# Power_Managment.net
KiCad netlist of a schematic drawn in Altium Designer
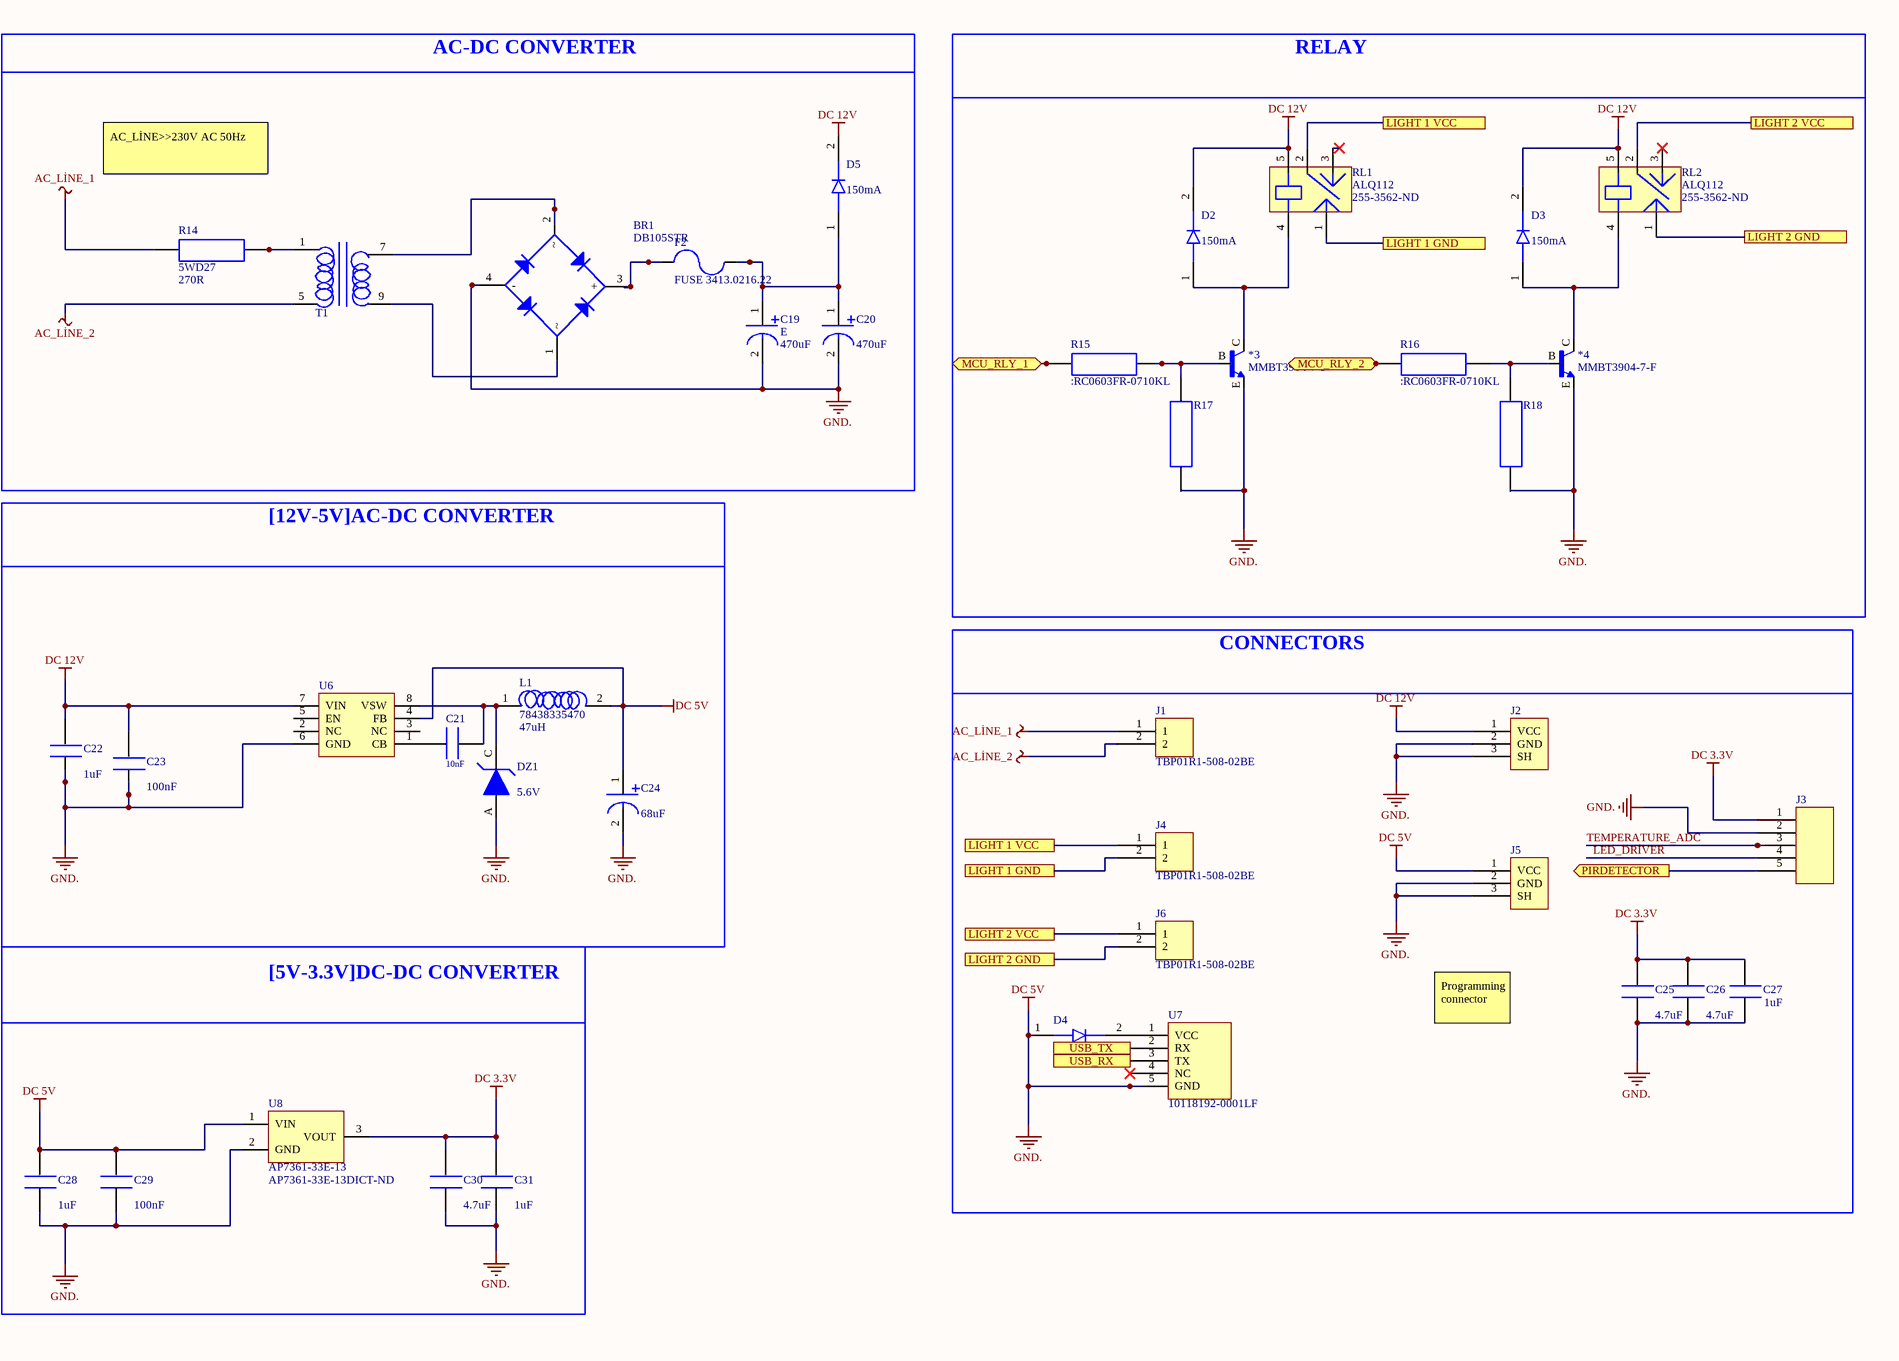
[diagram p0: Power Managment+.SchDoc, right]

(export (version "E")
  (design (tool "Eeschema 10.0.6"))
  (components
    (comp (ref "*3")
      (value "MMBT3904-7-F")
      (footprint "SOT23_F")
      (description "Transistor General Purpose BJT NPN 40 Volt 0.2A Automotive 3-Pin SOT-23")
      (fields (field (name "MANUFACTURER") "Diodes Zetex"))
      (libsource (lib "ALTİUM_PROJE.Integrated_Library1") (part "TRANS NPN 40V 0.2A SMD SOT23-3"))
    )
    (comp (ref "*4")
      (value "MMBT3904-7-F")
      (footprint "SOT23_F")
      (description "Transistor General Purpose BJT NPN 40 Volt 0.2A Automotive 3-Pin SOT-23")
      (fields (field (name "MANUFACTURER") "Diodes Zetex"))
      (libsource (lib "ALTİUM_PROJE.Integrated_Library1") (part "TRANS NPN 40V 0.2A SMD SOT23-3"))
    )
    (comp (ref "BR1")
      (value "DB105STR")
      (footprint "DB105STR")
      (description "Bridge Rect 1PHASE 600V 1A Db-s")
      (fields (field (name "MANUFACTURER") "Sangdest Microelectronics"))
      (libsource (lib "ALTİUM_PROJE.Integrated_Library1") (part "DB105STR"))
    )
    (comp (ref "C19")
      (value "E")
      (footprint "CAP_RADİAL_D10_P5")
      (description "Cap, 470UF, 50V, Alu Elec, Radial")
      (fields
        (field (name "MANUFACTURER") "KEMET")
        (field (name "MANUFACTURER PART NUMBER") "ESH477M050AH4AA")
        (field (name "CAPACITANCE") "470uF")
      )
      (libsource (lib "ALTİUM_PROJE.Integrated_Library1") (part "Cap, 470UF, 50V,"))
    )
    (comp (ref "C20")
      (value "ESH477M050AH4AA")
      (footprint "CAP_RADİAL_D10_P5")
      (description "Cap, 470UF, 50V, Alu Elec, Radial")
      (fields
        (field (name "MANUFACTURER") "KEMET")
        (field (name "TOLERANCE") "20%")
        (field (name "CAPACITANCE") "470uF")
      )
      (libsource (lib "ALTİUM_PROJE.Integrated_Library1") (part "Cap, 470UF, 50V,"))
    )
    (comp (ref "C21")
      (value "0603B103K160CT")
      (footprint "CAP_0603")
      (description "CAP CER 0603 0.01 F, 10%,")
      (fields
        (field (name "MANUFACTURER") "Walsin Technologies")
        (field (name "TOLERANCE") "10%")
        (field (name "CAPACITANCE") "10nF")
      )
      (libsource (lib "ALTİUM_PROJE.Integrated_Library1") (part "CAP CER 10nF"))
    )
    (comp (ref "C22")
      (value "CL21B105KBFNNNE")
      (footprint "CAP 0805")
      (description "Ceramic capacitor SMD-0805      %10 1UF")
      (fields
        (field (name "MANUFACTURER") "Samsung")
        (field (name "TOLERANCE") "10%")
        (field (name "CAPACITANCE") "1uF")
      )
      (libsource (lib "ALTİUM_PROJE.Integrated_Library1") (part "CAP CER 1UF"))
    )
    (comp (ref "C23")
      (value "C0603C104K5RACTU")
      (footprint "CAP_0603")
      (description "CAP CEP 100nF %10 0603 SMD")
      (fields
        (field (name "MANUFACTURER") "KEMET")
        (field (name "TOLERANCE") "10%")
        (field (name "CAPACITANCE") "100nF")
      )
      (libsource (lib "ALTİUM_PROJE.Integrated_Library1") (part "CAP CEP 100nF 0603"))
    )
    (comp (ref "C24")
      (value "EEV686M035A9HAA")
      (footprint "CAP_EEV")
      (description "Cap Aluminum Lytic 68uF 35V 20% (6.3 X 7.7mm) SMD 280mA 2000h 105C T/R")
      (fields
        (field (name "MANUFACTURER") "KEMET")
        (field (name "TOLERANCE") "20%")
        (field (name "CAPACITANCE") "68uF")
      )
      (libsource (lib "ALTİUM_PROJE.Integrated_Library1") (part "CAP ALUM 68UF 20% 35V SMD"))
    )
    (comp (ref "C25")
      (value "CL21A475KAQNNNE")
      (footprint "CAP 0805")
      (description "Cap Cer 4.7uF %10 0805")
      (fields
        (field (name "MANUFACTURER") "Samsung")
        (field (name "TOLERANCE") "10%")
        (field (name "CAPACITANCE") "4.7uF")
      )
      (libsource (lib "ALTİUM_PROJE.Integrated_Library1") (part "CAP CER_0805"))
    )
    (comp (ref "C26")
      (value "CL21A475KAQNNNE")
      (footprint "CAP 0805")
      (description "Cap Cer 4.7uF %10 0805")
      (fields
        (field (name "MANUFACTURER") "Samsung")
        (field (name "TOLERANCE") "10%")
        (field (name "CAPACITANCE") "4.7uF")
      )
      (libsource (lib "ALTİUM_PROJE.Integrated_Library1") (part "CAP CER_0805"))
    )
    (comp (ref "C27")
      (value "CL21B105KBFNNNE")
      (footprint "CAP 0805")
      (description "Ceramic capacitor SMD-0805      %10 1UF")
      (fields
        (field (name "MANUFACTURER") "Samsung")
        (field (name "TOLERANCE") "10%")
        (field (name "CAPACITANCE") "1uF")
      )
      (libsource (lib "ALTİUM_PROJE.Integrated_Library1") (part "CAP CER 1UF"))
    )
    (comp (ref "C28")
      (value "CL21B105KBFNNNE")
      (footprint "CAP 0805")
      (description "Ceramic capacitor SMD-0805      %10 1UF")
      (fields
        (field (name "MANUFACTURER") "Samsung")
        (field (name "TOLERANCE") "10%")
        (field (name "CAPACITANCE") "1uF")
      )
      (libsource (lib "ALTİUM_PROJE.Integrated_Library1") (part "CAP CER 1UF"))
    )
    (comp (ref "C29")
      (value "C0603C104K5RACTU")
      (footprint "CAP_0603")
      (description "CAP CEP 100nF %10 0603 SMD")
      (fields
        (field (name "MANUFACTURER") "KEMET")
        (field (name "TOLERANCE") "10%")
        (field (name "CAPACITANCE") "100nF")
      )
      (libsource (lib "ALTİUM_PROJE.Integrated_Library1") (part "CAP CEP 100nF 0603"))
    )
    (comp (ref "C30")
      (value "CL21A475KAQNNNE")
      (footprint "CAP 0805")
      (description "Cap Cer 4.7uF %10 0805")
      (fields
        (field (name "MANUFACTURER") "Samsung")
        (field (name "TOLERANCE") "10%")
        (field (name "CAPACITANCE") "4.7uF")
      )
      (libsource (lib "ALTİUM_PROJE.Integrated_Library1") (part "CAP CER_0805"))
    )
    (comp (ref "C31")
      (value "CL21B105KBFNNNE")
      (footprint "CAP 0805")
      (description "Ceramic capacitor SMD-0805      %10 1UF")
      (fields
        (field (name "MANUFACTURER") "Samsung")
        (field (name "TOLERANCE") "10%")
        (field (name "CAPACITANCE") "1uF")
      )
      (libsource (lib "ALTİUM_PROJE.Integrated_Library1") (part "CAP CER 1UF"))
    )
    (comp (ref "D2")
      (value "1N4148WS")
      (footprint "DİODE GEN")
      (description "Diode Small Signal Switching 100V 0.15A Automotive 2-Pin SOD-323F T/R")
      (fields
        (field (name "MANUFACTURER") "ON Semiconductor / Fairchild")
        (field (name "AVERAGE RECTIFIED CURRENT") "150mA")
      )
      (libsource (lib "ALTİUM_PROJE.Integrated_Library1") (part "DIODE GEN PURP 75V 150MA SOD323F"))
    )
    (comp (ref "D3")
      (value "1N4148WS")
      (footprint "DİODE GEN")
      (description "Diode Small Signal Switching 100V 0.15A Automotive 2-Pin SOD-323F T/R")
      (fields
        (field (name "MANUFACTURER") "ON Semiconductor / Fairchild")
        (field (name "AVERAGE RECTIFIED CURRENT") "150mA")
      )
      (libsource (lib "ALTİUM_PROJE.Integrated_Library1") (part "DIODE GEN PURP 75V 150MA SOD323F"))
    )
    (comp (ref "D4")
      (value "1N4148WS")
      (footprint "DİODE GEN")
      (description "Diode Small Signal Switching 100V 0.15A Automotive 2-Pin SOD-323F T/R")
      (fields (field (name "MANUFACTURER") "ON Semiconductor / Fairchild"))
      (libsource (lib "ALTİUM_PROJE.Integrated_Library1") (part "DIODE GEN PURP 75V 150MA SOD323F"))
    )
    (comp (ref "D5")
      (value "1N4148WS")
      (footprint "DİODE GEN")
      (description "Diode Small Signal Switching 100V 0.15A Automotive 2-Pin SOD-323F T/R")
      (fields
        (field (name "MANUFACTURER") "ON Semiconductor / Fairchild")
        (field (name "AVERAGE RECTIFIED CURRENT") "150mA")
      )
      (libsource (lib "ALTİUM_PROJE.Integrated_Library1") (part "DIODE GEN PURP 75V 150MA SOD323F"))
    )
    (comp (ref "DZ1")
      (value "Zener Diode 5.6V SMB")
      (footprint "ZEN DİOED SMD")
      (description "Diode, Zener, Vr 5.6V, If 200mA, Pkg SMB, Vf 1.5V, Tj +150degc, Pd 3W, Ir 66.9mA")
      (fields
        (field (name "MANUFACTURER") "ON Semiconductor")
        (field (name "MANUFACTURER PART NUMBER") "1SMB5919BT3G")
        (field (name "ZENER VOLTAGE") "5.6V")
      )
      (libsource (lib "ALTİUM_PROJE.Integrated_Library1") (part "Zener Diode 5.6V SMB"))
    )
    (comp (ref "F1")
      (value "FUSE 3413.0216.22")
      (footprint "FUSE 3413.0216.22")
      (description "Fuse Chip Fast Acting 1A 32V SMD Solder Pad 1206 Glass T/R VDE/cULus")
      (fields
        (field (name "MANUFACTURER") "Schurter")
        (field (name "MANUFACTURER PART NUMBER") "3413.0216.22")
      )
      (libsource (lib "ALTİUM_PROJE.Integrated_Library1") (part "FUSE 3413.0216.22"))
    )
    (comp (ref "F2")
      (value "FUSE 3413.0216.22")
      (footprint "FUSE 3413.0216.22")
      (description "Fuse Chip Fast Acting 1A 32V SMD Solder Pad 1206 Glass T/R VDE/cULus")
      (fields
        (field (name "MANUFACTURER") "Schurter")
        (field (name "MANUFACTURER PART NUMBER") "3413.0216.22")
      )
      (libsource (lib "ALTİUM_PROJE.Integrated_Library1") (part "FUSE 3413.0216.22"))
    )
    (comp (ref "J1")
      (value "TBP01R1-508-02BE")
      (footprint "TERMINAL BLOCK")
      (description "2~24 Poles, Pluggable, Receptacle, Horizontal, 5.08 Pitch, Terminal Block Connector")
      (fields (field (name "MANUFACTURER") "CUI Devices"))
      (libsource (lib "ALTİUM_PROJE.Integrated_Library1") (part "TERMINAL BLOCK"))
    )
    (comp (ref "J2")
      (value "PJ-037AH-SMT-TR")
      (footprint "jack")
      (description "2.0 x 6.3 mm, 5.0 A, Horizontal, Surface Mount (SMT), Dc Power Jack Connector")
      (fields (field (name "MANUFACTURER") "CUI"))
      (libsource (lib "ALTİUM_PROJE.Integrated_Library1") (part "PJ-037AH-SMT-TR"))
    )
    (comp (ref "J3")
      (value "SMH-105-02-L-S")
      (footprint "SMH-105")
      (description ".100 C.L. HORIZONTAL SMT SOCKET")
      (fields (field (name "MANUFACTURER") "Samtec"))
      (libsource (lib "ALTİUM_PROJE.Integrated_Library1") (part "PRO CONNECTER"))
    )
    (comp (ref "J4")
      (value "TBP01R1-508-02BE")
      (footprint "TERMINAL BLOCK")
      (description "2~24 Poles, Pluggable, Receptacle, Horizontal, 5.08 Pitch, Terminal Block Connector")
      (fields (field (name "MANUFACTURER") "CUI Devices"))
      (libsource (lib "ALTİUM_PROJE.Integrated_Library1") (part "TERMINAL BLOCK"))
    )
    (comp (ref "J5")
      (value "PJ-037AH-SMT-TR")
      (footprint "jack")
      (description "2.0 x 6.3 mm, 5.0 A, Horizontal, Surface Mount (SMT), Dc Power Jack Connector")
      (fields (field (name "MANUFACTURER") "CUI"))
      (libsource (lib "ALTİUM_PROJE.Integrated_Library1") (part "PJ-037AH-SMT-TR"))
    )
    (comp (ref "J6")
      (value "TBP01R1-508-02BE")
      (footprint "TERMINAL BLOCK")
      (description "2~24 Poles, Pluggable, Receptacle, Horizontal, 5.08 Pitch, Terminal Block Connector")
      (fields (field (name "MANUFACTURER") "CUI Devices"))
      (libsource (lib "ALTİUM_PROJE.Integrated_Library1") (part "TERMINAL BLOCK"))
    )
    (comp (ref "L1")
      (value "78438335470")
      (footprint "78438335470")
      (description "Fixed Ind 47UH 390MA 2.3 Ohm SMD")
      (fields
        (field (name "MANUFACTURER") "Wurth Electronics")
        (field (name "TOLERANCE") "30%")
        (field (name "INDUCTANCE") "47uH")
      )
      (libsource (lib "ALTİUM_PROJE.Integrated_Library1") (part "IND 47uH"))
    )
    (comp (ref "R14")
      (value "5WD27")
      (footprint "5WD27")
      (description "Resistor 5 Watt Cermet Wirewound Flameproof .27 Ohm 5% Axial Lead")
      (fields
        (field (name "MANUFACTURER") "NTE Electronics")
        (field (name "TOLERANCE") "5%")
        (field (name "RESISTANCE") "270R")
      )
      (libsource (lib "ALTİUM_PROJE.Integrated_Library1") (part "RES 0.27 OHM 5% 5W AXIAL"))
    )
    (comp (ref "R15")
      (value ":RC0603FR-0710KL")
      (footprint "RES_0603")
      (description "RES 10K %1 OHM 0603 SMD")
      (fields
        (field (name "MANUFACTURER") "Yageo")
        (field (name "MANUFACTURER PART NUMBER") "RC0603FR-0710KL")
      )
      (libsource (lib "") (part "RES 10K OHM 0603_1"))
    )
    (comp (ref "R16")
      (value ":RC0603FR-0710KL")
      (footprint "RES_0603")
      (description "RES 10K %1 OHM 0603 SMD")
      (fields
        (field (name "MANUFACTURER") "Yageo")
        (field (name "MANUFACTURER PART NUMBER") "RC0603FR-0710KL")
      )
      (libsource (lib "") (part "RES 10K OHM 0603_1"))
    )
    (comp (ref "R17")
      (value ":RC0603FR-0710KL")
      (footprint "RES_0603")
      (description "RES 10K %1 OHM 0603 SMD")
      (fields
        (field (name "MANUFACTURER") "Yageo")
        (field (name "MANUFACTURER PART NUMBER") "RC0603FR-0710KL")
      )
      (libsource (lib "ALTİUM_PROJE.Integrated_Library1") (part "RES 10K OHM 0603"))
    )
    (comp (ref "R18")
      (value ":RC0603FR-0710KL")
      (footprint "RES_0603")
      (description "RES 10K %1 OHM 0603 SMD")
      (fields
        (field (name "MANUFACTURER") "Yageo")
        (field (name "MANUFACTURER PART NUMBER") "RC0603FR-0710KL")
      )
      (libsource (lib "ALTİUM_PROJE.Integrated_Library1") (part "RES 10K OHM 0603"))
    )
    (comp (ref "RL1")
      (value "ALQ112")
      (footprint "ALQ112")
      (description "PANASONIC - ALQ112 - POWER RELAY, SPDT, 12VDC, 10A, THD")
      (fields (field (name "MANUFACTURER") "Panasonic") (field (name "SUPPLIER PART NUMBER 1") "255-3562-ND"))
      (libsource (lib "ALTİUM_PROJE.Integrated_Library1") (part "ALQ112"))
    )
    (comp (ref "RL2")
      (value "ALQ112")
      (footprint "ALQ112")
      (description "PANASONIC - ALQ112 - POWER RELAY, SPDT, 12VDC, 10A, THD")
      (fields (field (name "MANUFACTURER") "Panasonic") (field (name "SUPPLIER PART NUMBER 1") "255-3562-ND"))
      (libsource (lib "ALTİUM_PROJE.Integrated_Library1") (part "ALQ112"))
    )
    (comp (ref "T1")
      (value "BV302S12010-ZU")
      (footprint "BV302S12010-ZU")
      (description "Pwr Xfmr Laminated 1VA Th")
      (fields (field (name "MANUFACTURER") "Zettler Magnetics"))
      (libsource (lib "ALTİUM_PROJE.Integrated_Library1") (part "BV302S12010-ZU"))
    )
    (comp (ref "U6")
      (value "LM2675MX-12/NOPB")
      (footprint "SOIC8")
      (description "SIMPLE SWITCHER® 6.5V to 40V, 1A Low Component Count Step-Down Regulator 8-SOIC -40 to 125")
      (fields (field (name "MANUFACTURER") "TI National Semiconductor"))
      (libsource (lib "ALTİUM_PROJE.Integrated_Library1") (part "LM2675MX-12/NOPB"))
    )
    (comp (ref "U7")
      (value "10118192-0001LF")
      (footprint "MICRO USB")
      (description "FCI Right Angle Surface  USB 100 V ac; 1.8A")
      (fields (field (name "MANUFACTURER") "Amphenol ICC / FCI"))
      (libsource (lib "ALTİUM_PROJE.Integrated_Library1") (part "Micro USB"))
    )
    (comp (ref "U8")
      (value "AP7361-33E-13")
      (footprint "AP7361-33E-13")
      (description "AP7361 Series 3.3 V 1 A Low SMT Dropout Fixed-Mode Regulator - SOT-223")
      (fields
        (field (name "MANUFACTURER") "Diodes")
        (field (name "SUPPLIER PART NUMBER 1") "AP7361-33E-13DICT-ND")
      )
      (libsource (lib "ALTİUM_PROJE.Integrated_Library1") (part "AP7361-33E-13"))
    )
  )
  (nets
    (net (code "1") (name "/LED_DRİVER") (class "Default")
      (node (ref "J3") (pin "4") (pinfunction "4_4") (pintype "passive"))
    )
    (net (code "2") (name "/LIGHT 1 GND") (class "Default")
      (node (ref "J4") (pin "2") (pinfunction "2_2") (pintype "passive"))
      (node (ref "RL1") (pin "1") (pintype "passive"))
    )
    (net (code "3") (name "/LIGHT 1 VCC") (class "Default")
      (node (ref "J4") (pin "1") (pinfunction "1_1") (pintype "passive"))
      (node (ref "RL1") (pin "2") (pintype "passive"))
    )
    (net (code "4") (name "/LIGHT 2 GND") (class "Default")
      (node (ref "J6") (pin "2") (pinfunction "2_2") (pintype "passive"))
      (node (ref "RL2") (pin "1") (pintype "passive"))
    )
    (net (code "5") (name "/LIGHT 2 VCC") (class "Default")
      (node (ref "J6") (pin "1") (pinfunction "1_1") (pintype "passive"))
      (node (ref "RL2") (pin "2") (pintype "passive"))
    )
    (net (code "6") (name "/MCU_RLY_1") (class "Default")
      (node (ref "R15") (pin "1") (pinfunction "24_1") (pintype "passive"))
    )
    (net (code "8") (name "/PIRDETECTOR") (class "Default")
      (node (ref "J3") (pin "5") (pinfunction "5_5") (pintype "passive"))
    )
    (net (code "9") (name "/TEMPERATURE_ADC") (class "Default")
      (node (ref "J3") (pin "3") (pinfunction "3_3") (pintype "passive"))
    )
    (net (code "10") (name "/USB_RX") (class "Default")
      (node (ref "U7") (pin "3") (pinfunction "TX_3") (pintype "passive"))
    )
    (net (code "11") (name "/USB_TX") (class "Default")
      (node (ref "U7") (pin "2") (pinfunction "RX_2") (pintype "passive"))
    )
    (net (code "12") (name "AC_LİNE_1") (class "Default")
      (node (ref "J1") (pin "1") (pinfunction "1_1") (pintype "passive"))
      (node (ref "R14") (pin "1") (pinfunction "24_1") (pintype "passive"))
    )
    (net (code "13") (name "AC_LİNE_2") (class "Default")
      (node (ref "J1") (pin "2") (pinfunction "2_2") (pintype "passive"))
      (node (ref "T1") (pin "5") (pintype "passive"))
    )
    (net (code "14") (name "DC 3.3V") (class "Default")
      (node (ref "C25") (pin "2") (pinfunction "29_2") (pintype "passive"))
      (node (ref "C26") (pin "2") (pinfunction "29_2") (pintype "passive"))
      (node (ref "C27") (pin "2") (pinfunction "29_2") (pintype "passive"))
      (node (ref "C30") (pin "2") (pinfunction "29_2") (pintype "passive"))
      (node (ref "C31") (pin "2") (pinfunction "29_2") (pintype "passive"))
      (node (ref "J3") (pin "1") (pinfunction "1_1") (pintype "passive"))
      (node (ref "U8") (pin "3") (pinfunction "VOUT_3") (pintype "passive"))
    )
    (net (code "15") (name "DC 5V") (class "Default")
      (node (ref "*3") (pin "E") (pinfunction "E_E") (pintype "passive"))
      (node (ref "*4") (pin "E") (pinfunction "E_E") (pintype "passive"))
      (node (ref "BR1") (pin "4") (pinfunction "-_4") (pintype "passive"))
      (node (ref "C19") (pin "2") (pinfunction "1_2") (pintype "passive"))
      (node (ref "C20") (pin "2") (pinfunction "1_2") (pintype "passive"))
      (node (ref "C22") (pin "1") (pinfunction "28_1") (pintype "passive"))
      (node (ref "C23") (pin "1") (pinfunction "28_1") (pintype "passive"))
      (node (ref "C24") (pin "1") (pinfunction "0_1") (pintype "passive"))
      (node (ref "C24") (pin "2") (pinfunction "1_2") (pintype "passive"))
      (node (ref "C25") (pin "1") (pinfunction "28_1") (pintype "passive"))
      (node (ref "C26") (pin "1") (pinfunction "28_1") (pintype "passive"))
      (node (ref "C27") (pin "1") (pinfunction "28_1") (pintype "passive"))
      (node (ref "C28") (pin "1") (pinfunction "28_1") (pintype "passive"))
      (node (ref "C28") (pin "2") (pinfunction "29_2") (pintype "passive"))
      (node (ref "C29") (pin "1") (pinfunction "28_1") (pintype "passive"))
      (node (ref "C29") (pin "2") (pinfunction "29_2") (pintype "passive"))
      (node (ref "C30") (pin "1") (pinfunction "28_1") (pintype "passive"))
      (node (ref "C31") (pin "1") (pinfunction "28_1") (pintype "passive"))
      (node (ref "D4") (pin "1") (pinfunction "ANOT_1") (pintype "passive"))
      (node (ref "DZ1") (pin "A") (pinfunction "A_A") (pintype "passive"))
      (node (ref "J2") (pin "2") (pinfunction "GND_2") (pintype "passive"))
      (node (ref "J2") (pin "3") (pinfunction "SH_3") (pintype "passive"))
      (node (ref "J3") (pin "2") (pinfunction "2_2") (pintype "passive"))
      (node (ref "J5") (pin "1") (pinfunction "VCC_1") (pintype "passive"))
      (node (ref "J5") (pin "2") (pinfunction "GND_2") (pintype "passive"))
      (node (ref "J5") (pin "3") (pinfunction "SH_3") (pintype "passive"))
      (node (ref "L1") (pin "2") (pinfunction "2_2") (pintype "passive"))
      (node (ref "R17") (pin "1") (pinfunction "24_1") (pintype "passive"))
      (node (ref "R18") (pin "1") (pinfunction "24_1") (pintype "passive"))
      (node (ref "U6") (pin "4") (pinfunction "FB_4") (pintype "passive"))
      (node (ref "U6") (pin "6") (pinfunction "GND_6") (pintype "passive"))
      (node (ref "U7") (pin "5") (pinfunction "GND_5") (pintype "passive"))
      (node (ref "U8") (pin "1") (pinfunction "VIN_1") (pintype "passive"))
      (node (ref "U8") (pin "2") (pinfunction "GND_2") (pintype "passive"))
    )
    (net (code "16") (name "DC 12V") (class "Default")
      (node (ref "C22") (pin "2") (pinfunction "29_2") (pintype "passive"))
      (node (ref "C23") (pin "2") (pinfunction "29_2") (pintype "passive"))
      (node (ref "D2") (pin "2") (pinfunction "CAOTHODE_2") (pintype "passive"))
      (node (ref "D3") (pin "2") (pinfunction "CAOTHODE_2") (pintype "passive"))
      (node (ref "D5") (pin "2") (pinfunction "CAOTHODE_2") (pintype "passive"))
      (node (ref "J2") (pin "1") (pinfunction "VCC_1") (pintype "passive"))
      (node (ref "RL1") (pin "5") (pintype "passive"))
      (node (ref "RL2") (pin "5") (pintype "passive"))
      (node (ref "U6") (pin "7") (pinfunction "VIN_7") (pintype "passive"))
    )
    (net (code "17") (name "Net-(BR1-+)") (class "Default")
      (node (ref "BR1") (pin "3") (pinfunction "+_3") (pintype "passive"))
      (node (ref "F2") (pin "2") (pintype "passive"))
    )
    (net (code "18") (name "Net-(BR1-~-Pad1)") (class "Default")
      (node (ref "BR1") (pin "1") (pinfunction "~_1") (pintype "passive"))
      (node (ref "T1") (pin "9") (pintype "passive"))
    )
    (net (code "19") (name "Net-(BR1-~-Pad2)") (class "Default")
      (node (ref "BR1") (pin "2") (pinfunction "~_2") (pintype "passive"))
      (node (ref "T1") (pin "7") (pintype "passive"))
    )
    (net (code "20") (name "Net-(C21-28)") (class "Default")
      (node (ref "C21") (pin "1") (pinfunction "28_1") (pintype "passive"))
      (node (ref "DZ1") (pin "C") (pinfunction "C_C") (pintype "passive"))
      (node (ref "L1") (pin "1") (pinfunction "1_1") (pintype "passive"))
      (node (ref "U6") (pin "8") (pinfunction "VSW_8") (pintype "passive"))
    )
    (net (code "21") (name "Net-(C21-29)") (class "Default")
      (node (ref "C21") (pin "2") (pinfunction "29_2") (pintype "passive"))
      (node (ref "U6") (pin "1") (pinfunction "CB_1") (pintype "passive"))
    )
    (net (code "22") (name "Net-(D2-ANOT)") (class "Default")
      (node (ref "*3") (pin "C") (pinfunction "C_C") (pintype "passive"))
      (node (ref "D2") (pin "1") (pinfunction "ANOT_1") (pintype "passive"))
      (node (ref "RL1") (pin "4") (pintype "passive"))
    )
    (net (code "23") (name "Net-(D3-ANOT)") (class "Default")
      (node (ref "*4") (pin "C") (pinfunction "C_C") (pintype "passive"))
      (node (ref "D3") (pin "1") (pinfunction "ANOT_1") (pintype "passive"))
      (node (ref "RL2") (pin "4") (pintype "passive"))
    )
    (net (code "24") (name "Net-(D4-CAOTHODE)") (class "Default")
      (node (ref "D4") (pin "2") (pinfunction "CAOTHODE_2") (pintype "passive"))
      (node (ref "U7") (pin "1") (pinfunction "VCC_1") (pintype "passive"))
    )
    (net (code "25") (name "Net-(D5-ANOT)") (class "Default")
      (node (ref "C19") (pin "1") (pintype "passive"))
      (node (ref "C20") (pin "1") (pintype "passive"))
      (node (ref "D5") (pin "1") (pinfunction "ANOT_1") (pintype "passive"))
      (node (ref "F2") (pin "1") (pintype "passive"))
    )
    (net (code "26") (name "Net-(R14-25)") (class "Default")
      (node (ref "R14") (pin "2") (pinfunction "25_2") (pintype "passive"))
      (node (ref "T1") (pin "1") (pintype "passive"))
    )
    (net (code "27") (name "Net-(R15-25)") (class "Default")
      (node (ref "*3") (pin "B") (pinfunction "B_B") (pintype "passive"))
      (node (ref "R15") (pin "2") (pinfunction "25_2") (pintype "passive"))
      (node (ref "R17") (pin "2") (pinfunction "25_2") (pintype "passive"))
    )
    (net (code "28") (name "Net-(R16-25)") (class "Default")
      (node (ref "*4") (pin "B") (pinfunction "B_B") (pintype "passive"))
      (node (ref "R16") (pin "2") (pinfunction "25_2") (pintype "passive"))
      (node (ref "R18") (pin "2") (pinfunction "25_2") (pintype "passive"))
    )
    (net (code "29") (name "unconnected-(F1-Pad1)") (class "Default")
      (node (ref "F1") (pin "1") (pintype "passive"))
    )
    (net (code "30") (name "unconnected-(F1-Pad2)") (class "Default")
      (node (ref "F1") (pin "2") (pintype "passive"))
    )
    (net (code "31") (name "unconnected-(R16-24-Pad1)") (class "Default")
      (node (ref "R16") (pin "1") (pinfunction "24_1") (pintype "passive"))
    )
    (net (code "32") (name "unconnected-(RL1-Pad3)") (class "Default")
      (node (ref "RL1") (pin "3") (pintype "passive+no_connect"))
    )
    (net (code "33") (name "unconnected-(RL2-Pad3)") (class "Default")
      (node (ref "RL2") (pin "3") (pintype "passive+no_connect"))
    )
    (net (code "34") (name "unconnected-(U6-EN-Pad5)") (class "Default")
      (node (ref "U6") (pin "5") (pinfunction "EN_5") (pintype "passive"))
    )
    (net (code "35") (name "unconnected-(U6-NC-Pad2)") (class "Default")
      (node (ref "U6") (pin "2") (pinfunction "NC_2") (pintype "passive"))
    )
    (net (code "36") (name "unconnected-(U6-NC-Pad3)") (class "Default")
      (node (ref "U6") (pin "3") (pinfunction "NC_3") (pintype "passive"))
    )
    (net (code "37") (name "unconnected-(U7-NC-Pad4)") (class "Default")
      (node (ref "U7") (pin "4") (pinfunction "NC_4") (pintype "passive+no_connect"))
    )
  )
)
